# LightWalker.net
KiCad netlist of a schematic drawn in EAGLE
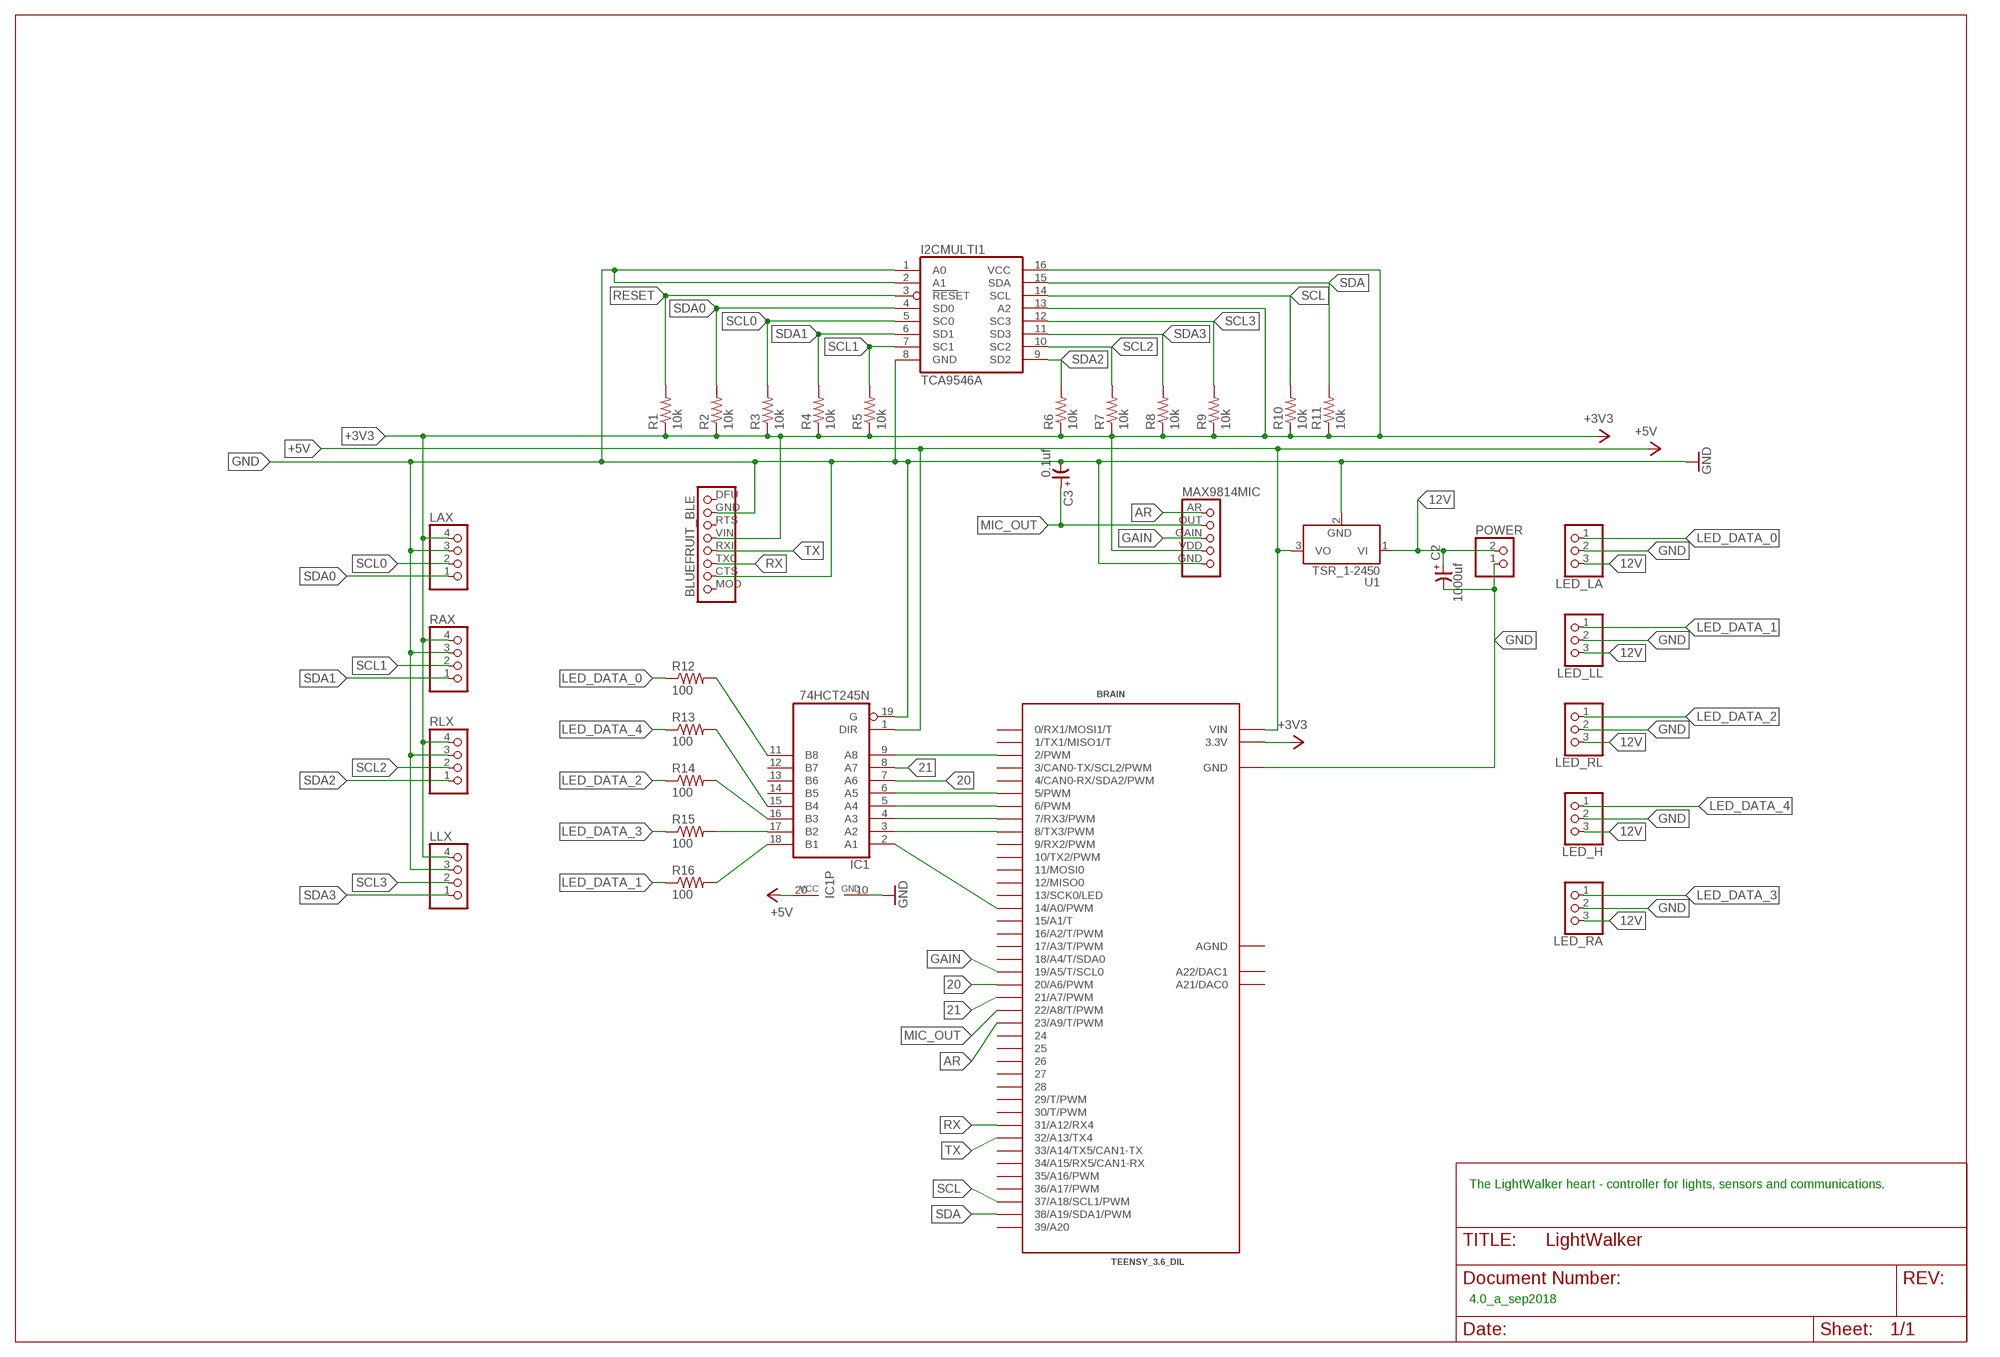
[diagram p0: schematic, sheet 1]

(export (version "E")
  (design (tool "Eeschema 10.0.6"))
  (components
    (comp (ref "BRAIN")
      (value "TEENSY_3.6_DIL")
      (footprint "eagle-import:TEENSY_3.6_DIL")
      (libsource (lib "eagle-import") (part "TEENSY_3.6_DIL"))
    )
    (comp (ref "C2")
      (value "1000uf")
      (footprint "eagle-import:SV-K")
      (libsource (lib "eagle-import") (part "CP-SV-K"))
    )
    (comp (ref "C3")
      (value "0.1uf")
      (footprint "eagle-import:3225")
      (libsource (lib "eagle-import") (part "cap-master.rpt_CP-3225"))
    )
    (comp (ref "I2CMULTI1")
      (value "TCA9546A")
      (footprint "eagle-import:SOIC16_LONGPAD")
      (libsource (lib "eagle-import") (part "TCA9546A"))
    )
    (comp (ref "IC1")
      (value "74HCT245N")
      (footprint "eagle-import:DIL20")
      (libsource (lib "eagle-import") (part "74245NHCT"))
    )
    (comp (ref "LAX")
      (value "2.54MM_TERMINAL_BLOCK-4")
      (footprint "eagle-import:TB_1X4")
      (libsource (lib "eagle-import") (part "2.54MM_TERMINAL_BLOCK-4"))
    )
    (comp (ref "LED_H")
      (value "2.54MM_TERMINAL_BLOCK-3")
      (footprint "eagle-import:TB_1X3")
      (libsource (lib "eagle-import") (part "2.54MM_TERMINAL_BLOCK-3"))
    )
    (comp (ref "LED_LA")
      (value "2.54MM_TERMINAL_BLOCK-3")
      (footprint "eagle-import:TB_1X3")
      (libsource (lib "eagle-import") (part "2.54MM_TERMINAL_BLOCK-3"))
    )
    (comp (ref "LED_LL")
      (value "2.54MM_TERMINAL_BLOCK-3")
      (footprint "eagle-import:TB_1X3")
      (libsource (lib "eagle-import") (part "2.54MM_TERMINAL_BLOCK-3"))
    )
    (comp (ref "LED_RA")
      (value "2.54MM_TERMINAL_BLOCK-3")
      (footprint "eagle-import:TB_1X3")
      (libsource (lib "eagle-import") (part "2.54MM_TERMINAL_BLOCK-3"))
    )
    (comp (ref "LED_RL")
      (value "2.54MM_TERMINAL_BLOCK-3")
      (footprint "eagle-import:TB_1X3")
      (libsource (lib "eagle-import") (part "2.54MM_TERMINAL_BLOCK-3"))
    )
    (comp (ref "LLX")
      (value "2.54MM_TERMINAL_BLOCK-4")
      (footprint "eagle-import:TB_1X4")
      (libsource (lib "eagle-import") (part "2.54MM_TERMINAL_BLOCK-4"))
    )
    (comp (ref "POWER")
      (value "2.54MM_TERMINAL_BLOCK-2")
      (footprint "eagle-import:TB_1X2")
      (libsource (lib "eagle-import") (part "2.54MM_TERMINAL_BLOCK-2"))
    )
    (comp (ref "R1")
      (value "10k")
      (footprint "eagle-import:R1206")
      (libsource (lib "eagle-import") (part "R-US_R1206"))
    )
    (comp (ref "R2")
      (value "10k")
      (footprint "eagle-import:R1206")
      (libsource (lib "eagle-import") (part "R-US_R1206"))
    )
    (comp (ref "R3")
      (value "10k")
      (footprint "eagle-import:R1206")
      (libsource (lib "eagle-import") (part "R-US_R1206"))
    )
    (comp (ref "R4")
      (value "10k")
      (footprint "eagle-import:R1206")
      (libsource (lib "eagle-import") (part "R-US_R1206"))
    )
    (comp (ref "R5")
      (value "10k")
      (footprint "eagle-import:R1206")
      (libsource (lib "eagle-import") (part "R-US_R1206"))
    )
    (comp (ref "R6")
      (value "10k")
      (footprint "eagle-import:R1206")
      (libsource (lib "eagle-import") (part "R-US_R1206"))
    )
    (comp (ref "R7")
      (value "10k")
      (footprint "eagle-import:R1206")
      (libsource (lib "eagle-import") (part "R-US_R1206"))
    )
    (comp (ref "R8")
      (value "10k")
      (footprint "eagle-import:R1206")
      (libsource (lib "eagle-import") (part "R-US_R1206"))
    )
    (comp (ref "R9")
      (value "10k")
      (footprint "eagle-import:R1206")
      (libsource (lib "eagle-import") (part "R-US_R1206"))
    )
    (comp (ref "R10")
      (value "10k")
      (footprint "eagle-import:R1206")
      (libsource (lib "eagle-import") (part "R-US_R1206"))
    )
    (comp (ref "R11")
      (value "10k")
      (footprint "eagle-import:R1206")
      (libsource (lib "eagle-import") (part "R-US_R1206"))
    )
    (comp (ref "R12")
      (value "100")
      (footprint "eagle-import:R1206")
      (libsource (lib "eagle-import") (part "R-US_R1206"))
    )
    (comp (ref "R13")
      (value "100")
      (footprint "eagle-import:R1206")
      (libsource (lib "eagle-import") (part "R-US_R1206"))
    )
    (comp (ref "R14")
      (value "100")
      (footprint "eagle-import:R1206")
      (libsource (lib "eagle-import") (part "R-US_R1206"))
    )
    (comp (ref "R15")
      (value "100")
      (footprint "eagle-import:R1206")
      (libsource (lib "eagle-import") (part "R-US_R1206"))
    )
    (comp (ref "R16")
      (value "100")
      (footprint "eagle-import:R1206")
      (libsource (lib "eagle-import") (part "R-US_R1206"))
    )
    (comp (ref "RAX")
      (value "2.54MM_TERMINAL_BLOCK-4")
      (footprint "eagle-import:TB_1X4")
      (libsource (lib "eagle-import") (part "2.54MM_TERMINAL_BLOCK-4"))
    )
    (comp (ref "RLX")
      (value "2.54MM_TERMINAL_BLOCK-4")
      (footprint "eagle-import:TB_1X4")
      (libsource (lib "eagle-import") (part "2.54MM_TERMINAL_BLOCK-4"))
    )
    (comp (ref "U$1")
      (value "BLUEFRUIT_BLE_UART_FRIENDALL")
      (footprint "eagle-import:BLUEFRUIT_BLE_UART_FRIEND_ALL")
      (libsource (lib "eagle-import") (part "BLUEFRUIT_BLE_UART_FRIENDALL"))
    )
    (comp (ref "U$4")
      (value "MAX9814MICALL")
      (footprint "eagle-import:MAX9814MIC")
      (libsource (lib "eagle-import") (part "MAX9814MICALL"))
    )
    (comp (ref "U1")
      (value "TSR_1-2450")
      (footprint "eagle-import:TSR-1")
      (libsource (lib "eagle-import") (part "TSR_1-2450"))
    )
  )
  (nets
    (net (code "1") (name "+3V3") (class "Default")
      (node (ref "BRAIN") (pin "3.3V") (pinfunction "3.3V_3.3V") (pintype "power_in"))
      (node (ref "BRAIN") (pin "3.3V3") (pinfunction "3.3V_3.3V3") (pintype "power_in"))
      (node (ref "I2CMULTI1") (pin "13") (pinfunction "A2_13") (pintype "input"))
      (node (ref "I2CMULTI1") (pin "16") (pinfunction "VCC_16") (pintype "power_in"))
      (node (ref "LAX") (pin "4") (pinfunction "4_4") (pintype "passive"))
      (node (ref "LLX") (pin "4") (pinfunction "4_4") (pintype "passive"))
      (node (ref "R1") (pin "1") (pinfunction "1_1") (pintype "passive"))
      (node (ref "R10") (pin "1") (pinfunction "1_1") (pintype "passive"))
      (node (ref "R11") (pin "1") (pinfunction "1_1") (pintype "passive"))
      (node (ref "R2") (pin "1") (pinfunction "1_1") (pintype "passive"))
      (node (ref "R3") (pin "1") (pinfunction "1_1") (pintype "passive"))
      (node (ref "R4") (pin "1") (pinfunction "1_1") (pintype "passive"))
      (node (ref "R5") (pin "1") (pinfunction "1_1") (pintype "passive"))
      (node (ref "R6") (pin "1") (pinfunction "1_1") (pintype "passive"))
      (node (ref "R7") (pin "1") (pinfunction "1_1") (pintype "passive"))
      (node (ref "R8") (pin "1") (pinfunction "1_1") (pintype "passive"))
      (node (ref "R9") (pin "1") (pinfunction "1_1") (pintype "passive"))
      (node (ref "RAX") (pin "4") (pinfunction "4_4") (pintype "passive"))
      (node (ref "RLX") (pin "4") (pinfunction "4_4") (pintype "passive"))
      (node (ref "U$1") (pin "VIN") (pinfunction "VIN_VIN") (pintype "power_in"))
      (node (ref "U$4") (pin "VDD") (pinfunction "VDD_VDD") (pintype "power_in"))
    )
    (net (code "2") (name "+5V") (class "Default")
      (node (ref "BRAIN") (pin "VIN") (pinfunction "VIN_VIN") (pintype "power_in"))
      (node (ref "IC1") (pin "1") (pinfunction "DIR_1") (pintype "input"))
      (node (ref "IC1") (pin "20") (pinfunction "VCC_20") (pintype "power_in"))
      (node (ref "U1") (pin "3") (pinfunction "VO_3") (pintype "power_in"))
    )
    (net (code "3") (name "/AGND") (class "Default")
      (node (ref "BRAIN") (pin "AGND") (pinfunction "AGND_AGND") (pintype "power_in"))
    )
    (net (code "4") (name "12V") (class "Default")
      (node (ref "C2") (pin "+") (pinfunction "+_+") (pintype "passive"))
      (node (ref "LED_H") (pin "3") (pinfunction "1_3") (pintype "passive"))
      (node (ref "LED_LA") (pin "3") (pinfunction "1_3") (pintype "passive"))
      (node (ref "LED_LL") (pin "3") (pinfunction "1_3") (pintype "passive"))
      (node (ref "LED_RA") (pin "3") (pinfunction "1_3") (pintype "passive"))
      (node (ref "LED_RL") (pin "3") (pinfunction "1_3") (pintype "passive"))
      (node (ref "POWER") (pin "2") (pinfunction "1_2") (pintype "passive"))
      (node (ref "U1") (pin "1") (pinfunction "VI_1") (pintype "power_in"))
    )
    (net (code "5") (name "20") (class "Default")
      (node (ref "BRAIN") (pin "20/A6") (pinfunction "20/A6/PWM_20/A6") (pintype "bidirectional"))
      (node (ref "IC1") (pin "7") (pinfunction "A6_7") (pintype "bidirectional"))
    )
    (net (code "6") (name "21") (class "Default")
      (node (ref "BRAIN") (pin "21/A7") (pinfunction "21/A7/PWM_21/A7") (pintype "bidirectional"))
      (node (ref "IC1") (pin "8") (pinfunction "A7_8") (pintype "bidirectional"))
    )
    (net (code "7") (name "AR") (class "Default")
      (node (ref "BRAIN") (pin "23/A9") (pinfunction "23/A9/T/PWM_23/A9") (pintype "bidirectional"))
      (node (ref "U$4") (pin "AR") (pinfunction "AR_AR") (pintype "input"))
    )
    (net (code "8") (name "GAIN") (class "Default")
      (node (ref "BRAIN") (pin "19/A5") (pinfunction "19/A5/T/SCL0_19/A5") (pintype "bidirectional"))
      (node (ref "U$4") (pin "GAIN") (pinfunction "GAIN_GAIN") (pintype "input"))
    )
    (net (code "9") (name "GND") (class "Default")
      (node (ref "BRAIN") (pin "GND") (pinfunction "GND_GND") (pintype "power_in"))
      (node (ref "BRAIN") (pin "GND1") (pinfunction "GND_GND1") (pintype "power_in"))
      (node (ref "C2") (pin "-") (pinfunction "-_-") (pintype "passive"))
      (node (ref "C3") (pin "2") (pinfunction "-_2") (pintype "passive"))
      (node (ref "I2CMULTI1") (pin "1") (pinfunction "A0_1") (pintype "input"))
      (node (ref "I2CMULTI1") (pin "2") (pinfunction "A1_2") (pintype "input"))
      (node (ref "I2CMULTI1") (pin "8") (pinfunction "GND_8") (pintype "power_in"))
      (node (ref "IC1") (pin "10") (pinfunction "GND_10") (pintype "power_in"))
      (node (ref "IC1") (pin "19") (pinfunction "G_19") (pintype "input"))
      (node (ref "LAX") (pin "3") (pinfunction "3_3") (pintype "passive"))
      (node (ref "LED_H") (pin "2") (pinfunction "2_2") (pintype "passive"))
      (node (ref "LED_LA") (pin "2") (pinfunction "2_2") (pintype "passive"))
      (node (ref "LED_LL") (pin "2") (pinfunction "2_2") (pintype "passive"))
      (node (ref "LED_RA") (pin "2") (pinfunction "2_2") (pintype "passive"))
      (node (ref "LED_RL") (pin "2") (pinfunction "2_2") (pintype "passive"))
      (node (ref "LLX") (pin "3") (pinfunction "3_3") (pintype "passive"))
      (node (ref "POWER") (pin "1") (pinfunction "2_1") (pintype "passive"))
      (node (ref "RAX") (pin "3") (pinfunction "3_3") (pintype "passive"))
      (node (ref "RLX") (pin "3") (pinfunction "3_3") (pintype "passive"))
      (node (ref "U$1") (pin "CTS") (pinfunction "CTS_CTS") (pintype "input"))
      (node (ref "U$1") (pin "GND") (pinfunction "GND_GND") (pintype "power_in"))
      (node (ref "U$4") (pin "GND") (pinfunction "GND_GND") (pintype "power_in"))
      (node (ref "U1") (pin "2") (pinfunction "GND_2") (pintype "power_in"))
    )
    (net (code "10") (name "LED_DATA_0") (class "Default")
      (node (ref "LED_LA") (pin "1") (pinfunction "3_1") (pintype "passive"))
      (node (ref "R12") (pin "1") (pinfunction "1_1") (pintype "passive"))
    )
    (net (code "11") (name "LED_DATA_1") (class "Default")
      (node (ref "LED_LL") (pin "1") (pinfunction "3_1") (pintype "passive"))
      (node (ref "R16") (pin "1") (pinfunction "1_1") (pintype "passive"))
    )
    (net (code "12") (name "LED_DATA_2") (class "Default")
      (node (ref "LED_RL") (pin "1") (pinfunction "3_1") (pintype "passive"))
      (node (ref "R14") (pin "1") (pinfunction "1_1") (pintype "passive"))
    )
    (net (code "13") (name "LED_DATA_3") (class "Default")
      (node (ref "LED_RA") (pin "1") (pinfunction "3_1") (pintype "passive"))
      (node (ref "R15") (pin "1") (pinfunction "1_1") (pintype "passive"))
    )
    (net (code "14") (name "LED_DATA_4") (class "Default")
      (node (ref "LED_H") (pin "1") (pinfunction "3_1") (pintype "passive"))
      (node (ref "R13") (pin "1") (pinfunction "1_1") (pintype "passive"))
    )
    (net (code "15") (name "MIC_OUT") (class "Default")
      (node (ref "BRAIN") (pin "22/A8") (pinfunction "22/A8/T/PWM_22/A8") (pintype "bidirectional"))
      (node (ref "C3") (pin "1") (pinfunction "+_1") (pintype "passive"))
      (node (ref "U$4") (pin "OUT") (pinfunction "OUT_OUT") (pintype "output"))
    )
    (net (code "16") (name "Net-(BRAIN-2{slash}PWM)") (class "Default")
      (node (ref "BRAIN") (pin "2") (pinfunction "2/PWM_2") (pintype "bidirectional"))
      (node (ref "IC1") (pin "9") (pinfunction "A8_9") (pintype "bidirectional"))
    )
    (net (code "17") (name "Net-(BRAIN-5{slash}PWM)") (class "Default")
      (node (ref "BRAIN") (pin "5") (pinfunction "5/PWM_5") (pintype "bidirectional"))
      (node (ref "IC1") (pin "6") (pinfunction "A5_6") (pintype "bidirectional"))
    )
    (net (code "18") (name "Net-(BRAIN-6{slash}PWM)") (class "Default")
      (node (ref "BRAIN") (pin "6") (pinfunction "6/PWM_6") (pintype "bidirectional"))
      (node (ref "IC1") (pin "5") (pinfunction "A4_5") (pintype "bidirectional"))
    )
    (net (code "19") (name "Net-(BRAIN-7{slash}RX3{slash}PWM)") (class "Default")
      (node (ref "BRAIN") (pin "7") (pinfunction "7/RX3/PWM_7") (pintype "bidirectional"))
      (node (ref "IC1") (pin "4") (pinfunction "A3_4") (pintype "bidirectional"))
    )
    (net (code "20") (name "Net-(BRAIN-8{slash}TX3{slash}PWM)") (class "Default")
      (node (ref "BRAIN") (pin "8") (pinfunction "8/TX3/PWM_8") (pintype "bidirectional"))
      (node (ref "IC1") (pin "3") (pinfunction "A2_3") (pintype "bidirectional"))
    )
    (net (code "21") (name "Net-(BRAIN-14{slash}A0{slash}PWM)") (class "Default")
      (node (ref "BRAIN") (pin "14/A0") (pinfunction "14/A0/PWM_14/A0") (pintype "bidirectional"))
      (node (ref "IC1") (pin "2") (pinfunction "A1_2") (pintype "bidirectional"))
    )
    (net (code "22") (name "Net-(IC1A-B1)") (class "Default")
      (node (ref "IC1") (pin "18") (pinfunction "B1_18") (pintype "bidirectional"))
      (node (ref "R16") (pin "2") (pinfunction "2_2") (pintype "passive"))
    )
    (net (code "23") (name "Net-(IC1A-B2)") (class "Default")
      (node (ref "IC1") (pin "17") (pinfunction "B2_17") (pintype "bidirectional"))
      (node (ref "R15") (pin "2") (pinfunction "2_2") (pintype "passive"))
    )
    (net (code "24") (name "Net-(IC1A-B3)") (class "Default")
      (node (ref "IC1") (pin "16") (pinfunction "B3_16") (pintype "bidirectional"))
      (node (ref "R14") (pin "2") (pinfunction "2_2") (pintype "passive"))
    )
    (net (code "25") (name "Net-(IC1A-B4)") (class "Default")
      (node (ref "IC1") (pin "15") (pinfunction "B4_15") (pintype "bidirectional"))
      (node (ref "R13") (pin "2") (pinfunction "2_2") (pintype "passive"))
    )
    (net (code "26") (name "Net-(IC1A-B8)") (class "Default")
      (node (ref "IC1") (pin "11") (pinfunction "B8_11") (pintype "bidirectional"))
      (node (ref "R12") (pin "2") (pinfunction "2_2") (pintype "passive"))
    )
    (net (code "27") (name "RESET") (class "Default")
      (node (ref "I2CMULTI1") (pin "3") (pinfunction "RESET_3") (pintype "input"))
      (node (ref "R1") (pin "2") (pinfunction "2_2") (pintype "passive"))
    )
    (net (code "28") (name "RX") (class "Default")
      (node (ref "BRAIN") (pin "31/A12") (pinfunction "31/A12/RX4_31/A12") (pintype "bidirectional"))
      (node (ref "U$1") (pin "TX0") (pinfunction "TXO_TX0") (pintype "output"))
    )
    (net (code "29") (name "SCL") (class "Default")
      (node (ref "BRAIN") (pin "37/A18") (pinfunction "37/A18/SCL1/PWM_37/A18") (pintype "bidirectional"))
      (node (ref "I2CMULTI1") (pin "14") (pinfunction "SCL_14") (pintype "input"))
      (node (ref "R10") (pin "2") (pinfunction "2_2") (pintype "passive"))
    )
    (net (code "30") (name "SCL0") (class "Default")
      (node (ref "I2CMULTI1") (pin "5") (pinfunction "SC0_5") (pintype "output"))
      (node (ref "LAX") (pin "2") (pinfunction "2_2") (pintype "passive"))
      (node (ref "R3") (pin "2") (pinfunction "2_2") (pintype "passive"))
    )
    (net (code "31") (name "SCL1") (class "Default")
      (node (ref "I2CMULTI1") (pin "7") (pinfunction "SC1_7") (pintype "output"))
      (node (ref "R5") (pin "2") (pinfunction "2_2") (pintype "passive"))
      (node (ref "RAX") (pin "2") (pinfunction "2_2") (pintype "passive"))
    )
    (net (code "32") (name "SCL2") (class "Default")
      (node (ref "I2CMULTI1") (pin "10") (pinfunction "SC2_10") (pintype "output"))
      (node (ref "R7") (pin "2") (pinfunction "2_2") (pintype "passive"))
      (node (ref "RLX") (pin "2") (pinfunction "2_2") (pintype "passive"))
    )
    (net (code "33") (name "SCL3") (class "Default")
      (node (ref "I2CMULTI1") (pin "12") (pinfunction "SC3_12") (pintype "output"))
      (node (ref "LLX") (pin "2") (pinfunction "2_2") (pintype "passive"))
      (node (ref "R9") (pin "2") (pinfunction "2_2") (pintype "passive"))
    )
    (net (code "34") (name "SDA") (class "Default")
      (node (ref "BRAIN") (pin "38/A19") (pinfunction "38/A19/SDA1/PWM_38/A19") (pintype "bidirectional"))
      (node (ref "I2CMULTI1") (pin "15") (pinfunction "SDA_15") (pintype "bidirectional"))
      (node (ref "R11") (pin "2") (pinfunction "2_2") (pintype "passive"))
    )
    (net (code "35") (name "SDA0") (class "Default")
      (node (ref "I2CMULTI1") (pin "4") (pinfunction "SD0_4") (pintype "bidirectional"))
      (node (ref "LAX") (pin "1") (pinfunction "1_1") (pintype "passive"))
      (node (ref "R2") (pin "2") (pinfunction "2_2") (pintype "passive"))
    )
    (net (code "36") (name "SDA1") (class "Default")
      (node (ref "I2CMULTI1") (pin "6") (pinfunction "SD1_6") (pintype "bidirectional"))
      (node (ref "R4") (pin "2") (pinfunction "2_2") (pintype "passive"))
      (node (ref "RAX") (pin "1") (pinfunction "1_1") (pintype "passive"))
    )
    (net (code "37") (name "SDA2") (class "Default")
      (node (ref "I2CMULTI1") (pin "9") (pinfunction "SD2_9") (pintype "bidirectional"))
      (node (ref "R6") (pin "2") (pinfunction "2_2") (pintype "passive"))
      (node (ref "RLX") (pin "1") (pinfunction "1_1") (pintype "passive"))
    )
    (net (code "38") (name "SDA3") (class "Default")
      (node (ref "I2CMULTI1") (pin "11") (pinfunction "SD3_11") (pintype "bidirectional"))
      (node (ref "LLX") (pin "1") (pinfunction "1_1") (pintype "passive"))
      (node (ref "R8") (pin "2") (pinfunction "2_2") (pintype "passive"))
    )
    (net (code "39") (name "TX") (class "Default")
      (node (ref "BRAIN") (pin "32/A13") (pinfunction "32/A13/TX4_32/A13") (pintype "bidirectional"))
      (node (ref "U$1") (pin "RXI") (pinfunction "RXI_RXI") (pintype "input"))
    )
    (net (code "40") (name "unconnected-(BRAIN-0{slash}RX1{slash}MOSI1{slash}T-Pad0)") (class "Default")
      (node (ref "BRAIN") (pin "0") (pinfunction "0/RX1/MOSI1/T_0") (pintype "bidirectional"))
    )
    (net (code "41") (name "unconnected-(BRAIN-1{slash}TX1{slash}MISO1{slash}T-Pad1)") (class "Default")
      (node (ref "BRAIN") (pin "1") (pinfunction "1/TX1/MISO1/T_1") (pintype "bidirectional"))
    )
    (net (code "42") (name "unconnected-(BRAIN-3{slash}CAN0-TX{slash}SCL2{slash}PWM-Pad3)") (class "Default")
      (node (ref "BRAIN") (pin "3") (pinfunction "3/CAN0-TX/SCL2/PWM_3") (pintype "bidirectional"))
    )
    (net (code "43") (name "unconnected-(BRAIN-4{slash}CAN0-RX{slash}SDA2{slash}PWM-Pad4)") (class "Default")
      (node (ref "BRAIN") (pin "4") (pinfunction "4/CAN0-RX/SDA2/PWM_4") (pintype "bidirectional"))
    )
    (net (code "44") (name "unconnected-(BRAIN-9{slash}RX2{slash}PWM-Pad9)") (class "Default")
      (node (ref "BRAIN") (pin "9") (pinfunction "9/RX2/PWM_9") (pintype "bidirectional"))
    )
    (net (code "45") (name "unconnected-(BRAIN-10{slash}TX2{slash}PWM-Pad10)") (class "Default")
      (node (ref "BRAIN") (pin "10") (pinfunction "10/TX2/PWM_10") (pintype "bidirectional"))
    )
    (net (code "46") (name "unconnected-(BRAIN-11{slash}MOSI0-Pad11)") (class "Default")
      (node (ref "BRAIN") (pin "11") (pinfunction "11/MOSI0_11") (pintype "bidirectional"))
    )
    (net (code "47") (name "unconnected-(BRAIN-12{slash}MISO0-Pad12)") (class "Default")
      (node (ref "BRAIN") (pin "12") (pinfunction "12/MISO0_12") (pintype "bidirectional"))
    )
    (net (code "48") (name "unconnected-(BRAIN-13{slash}SCK0{slash}LED-Pad13)") (class "Default")
      (node (ref "BRAIN") (pin "13") (pinfunction "13/SCK0/LED_13") (pintype "bidirectional"))
    )
    (net (code "49") (name "unconnected-(BRAIN-15{slash}A1{slash}T-Pad15{slash}A1)") (class "Default")
      (node (ref "BRAIN") (pin "15/A1") (pinfunction "15/A1/T_15/A1") (pintype "bidirectional"))
    )
    (net (code "50") (name "unconnected-(BRAIN-16{slash}A2{slash}T{slash}PWM-Pad16{slash}A2)") (class "Default")
      (node (ref "BRAIN") (pin "16/A2") (pinfunction "16/A2/T/PWM_16/A2") (pintype "bidirectional"))
    )
    (net (code "51") (name "unconnected-(BRAIN-17{slash}A3{slash}T{slash}PWM-Pad17{slash}A3)") (class "Default")
      (node (ref "BRAIN") (pin "17/A3") (pinfunction "17/A3/T/PWM_17/A3") (pintype "bidirectional"))
    )
    (net (code "52") (name "unconnected-(BRAIN-18{slash}A4{slash}T{slash}SDA0-Pad18{slash}A4)") (class "Default")
      (node (ref "BRAIN") (pin "18/A4") (pinfunction "18/A4/T/SDA0_18/A4") (pintype "bidirectional"))
    )
    (net (code "53") (name "unconnected-(BRAIN-29{slash}T{slash}PWM-Pad29)") (class "Default")
      (node (ref "BRAIN") (pin "29") (pinfunction "29/T/PWM_29") (pintype "bidirectional"))
    )
    (net (code "54") (name "unconnected-(BRAIN-30{slash}T{slash}PWM-Pad30)") (class "Default")
      (node (ref "BRAIN") (pin "30") (pinfunction "30/T/PWM_30") (pintype "bidirectional"))
    )
    (net (code "55") (name "unconnected-(BRAIN-33{slash}A14{slash}TX5{slash}CAN1-TX-Pad33{slash}A14)") (class "Default")
      (node (ref "BRAIN") (pin "33/A14") (pinfunction "33/A14/TX5/CAN1-TX_33/A14") (pintype "bidirectional"))
    )
    (net (code "56") (name "unconnected-(BRAIN-34{slash}A15{slash}RX5{slash}CAN1-RX-Pad34{slash}A15)") (class "Default")
      (node (ref "BRAIN") (pin "34/A15") (pinfunction "34/A15/RX5/CAN1-RX_34/A15") (pintype "bidirectional"))
    )
    (net (code "57") (name "unconnected-(BRAIN-35{slash}A16{slash}PWM-Pad35{slash}A16)") (class "Default")
      (node (ref "BRAIN") (pin "35/A16") (pinfunction "35/A16/PWM_35/A16") (pintype "bidirectional"))
    )
    (net (code "58") (name "unconnected-(BRAIN-36{slash}A17{slash}PWM-Pad36{slash}A17)") (class "Default")
      (node (ref "BRAIN") (pin "36/A17") (pinfunction "36/A17/PWM_36/A17") (pintype "bidirectional"))
    )
    (net (code "59") (name "unconnected-(BRAIN-A21{slash}DAC0-PadA21)") (class "Default")
      (node (ref "BRAIN") (pin "A21") (pinfunction "A21/DAC0_A21") (pintype "bidirectional"))
    )
    (net (code "60") (name "unconnected-(BRAIN-A22{slash}DAC1-PadA22)") (class "Default")
      (node (ref "BRAIN") (pin "A22") (pinfunction "A22/DAC1_A22") (pintype "bidirectional"))
    )
    (net (code "61") (name "unconnected-(BRAIN-Pad24)") (class "Default")
      (node (ref "BRAIN") (pin "24") (pinfunction "24_24") (pintype "bidirectional"))
    )
    (net (code "62") (name "unconnected-(BRAIN-Pad25)") (class "Default")
      (node (ref "BRAIN") (pin "25") (pinfunction "25_25") (pintype "bidirectional"))
    )
    (net (code "63") (name "unconnected-(BRAIN-Pad26)") (class "Default")
      (node (ref "BRAIN") (pin "26") (pinfunction "26_26") (pintype "bidirectional"))
    )
    (net (code "64") (name "unconnected-(BRAIN-Pad27)") (class "Default")
      (node (ref "BRAIN") (pin "27") (pinfunction "27_27") (pintype "bidirectional"))
    )
    (net (code "65") (name "unconnected-(BRAIN-Pad28)") (class "Default")
      (node (ref "BRAIN") (pin "28") (pinfunction "28_28") (pintype "bidirectional"))
    )
    (net (code "66") (name "unconnected-(BRAIN-Pad39{slash}A20)") (class "Default")
      (node (ref "BRAIN") (pin "39/A20") (pinfunction "39/A20_39/A20") (pintype "bidirectional"))
    )
    (net (code "67") (name "unconnected-(IC1A-B5-Pad14)") (class "Default")
      (node (ref "IC1") (pin "14") (pinfunction "B5_14") (pintype "bidirectional"))
    )
    (net (code "68") (name "unconnected-(IC1A-B6-Pad13)") (class "Default")
      (node (ref "IC1") (pin "13") (pinfunction "B6_13") (pintype "bidirectional"))
    )
    (net (code "69") (name "unconnected-(IC1A-B7-Pad12)") (class "Default")
      (node (ref "IC1") (pin "12") (pinfunction "B7_12") (pintype "bidirectional"))
    )
    (net (code "70") (name "unconnected-(U$1-PadDFU)") (class "Default")
      (node (ref "U$1") (pin "DFU") (pinfunction "DFU_DFU") (pintype "bidirectional"))
    )
    (net (code "71") (name "unconnected-(U$1-PadMOD)") (class "Default")
      (node (ref "U$1") (pin "MOD") (pinfunction "MOD_MOD") (pintype "bidirectional"))
    )
    (net (code "72") (name "unconnected-(U$1-PadRTS)") (class "Default")
      (node (ref "U$1") (pin "RTS") (pinfunction "RTS_RTS") (pintype "output"))
    )
  )
)
